# piezo_amplifier.net
KiCad netlist of a schematic drawn in EAGLE
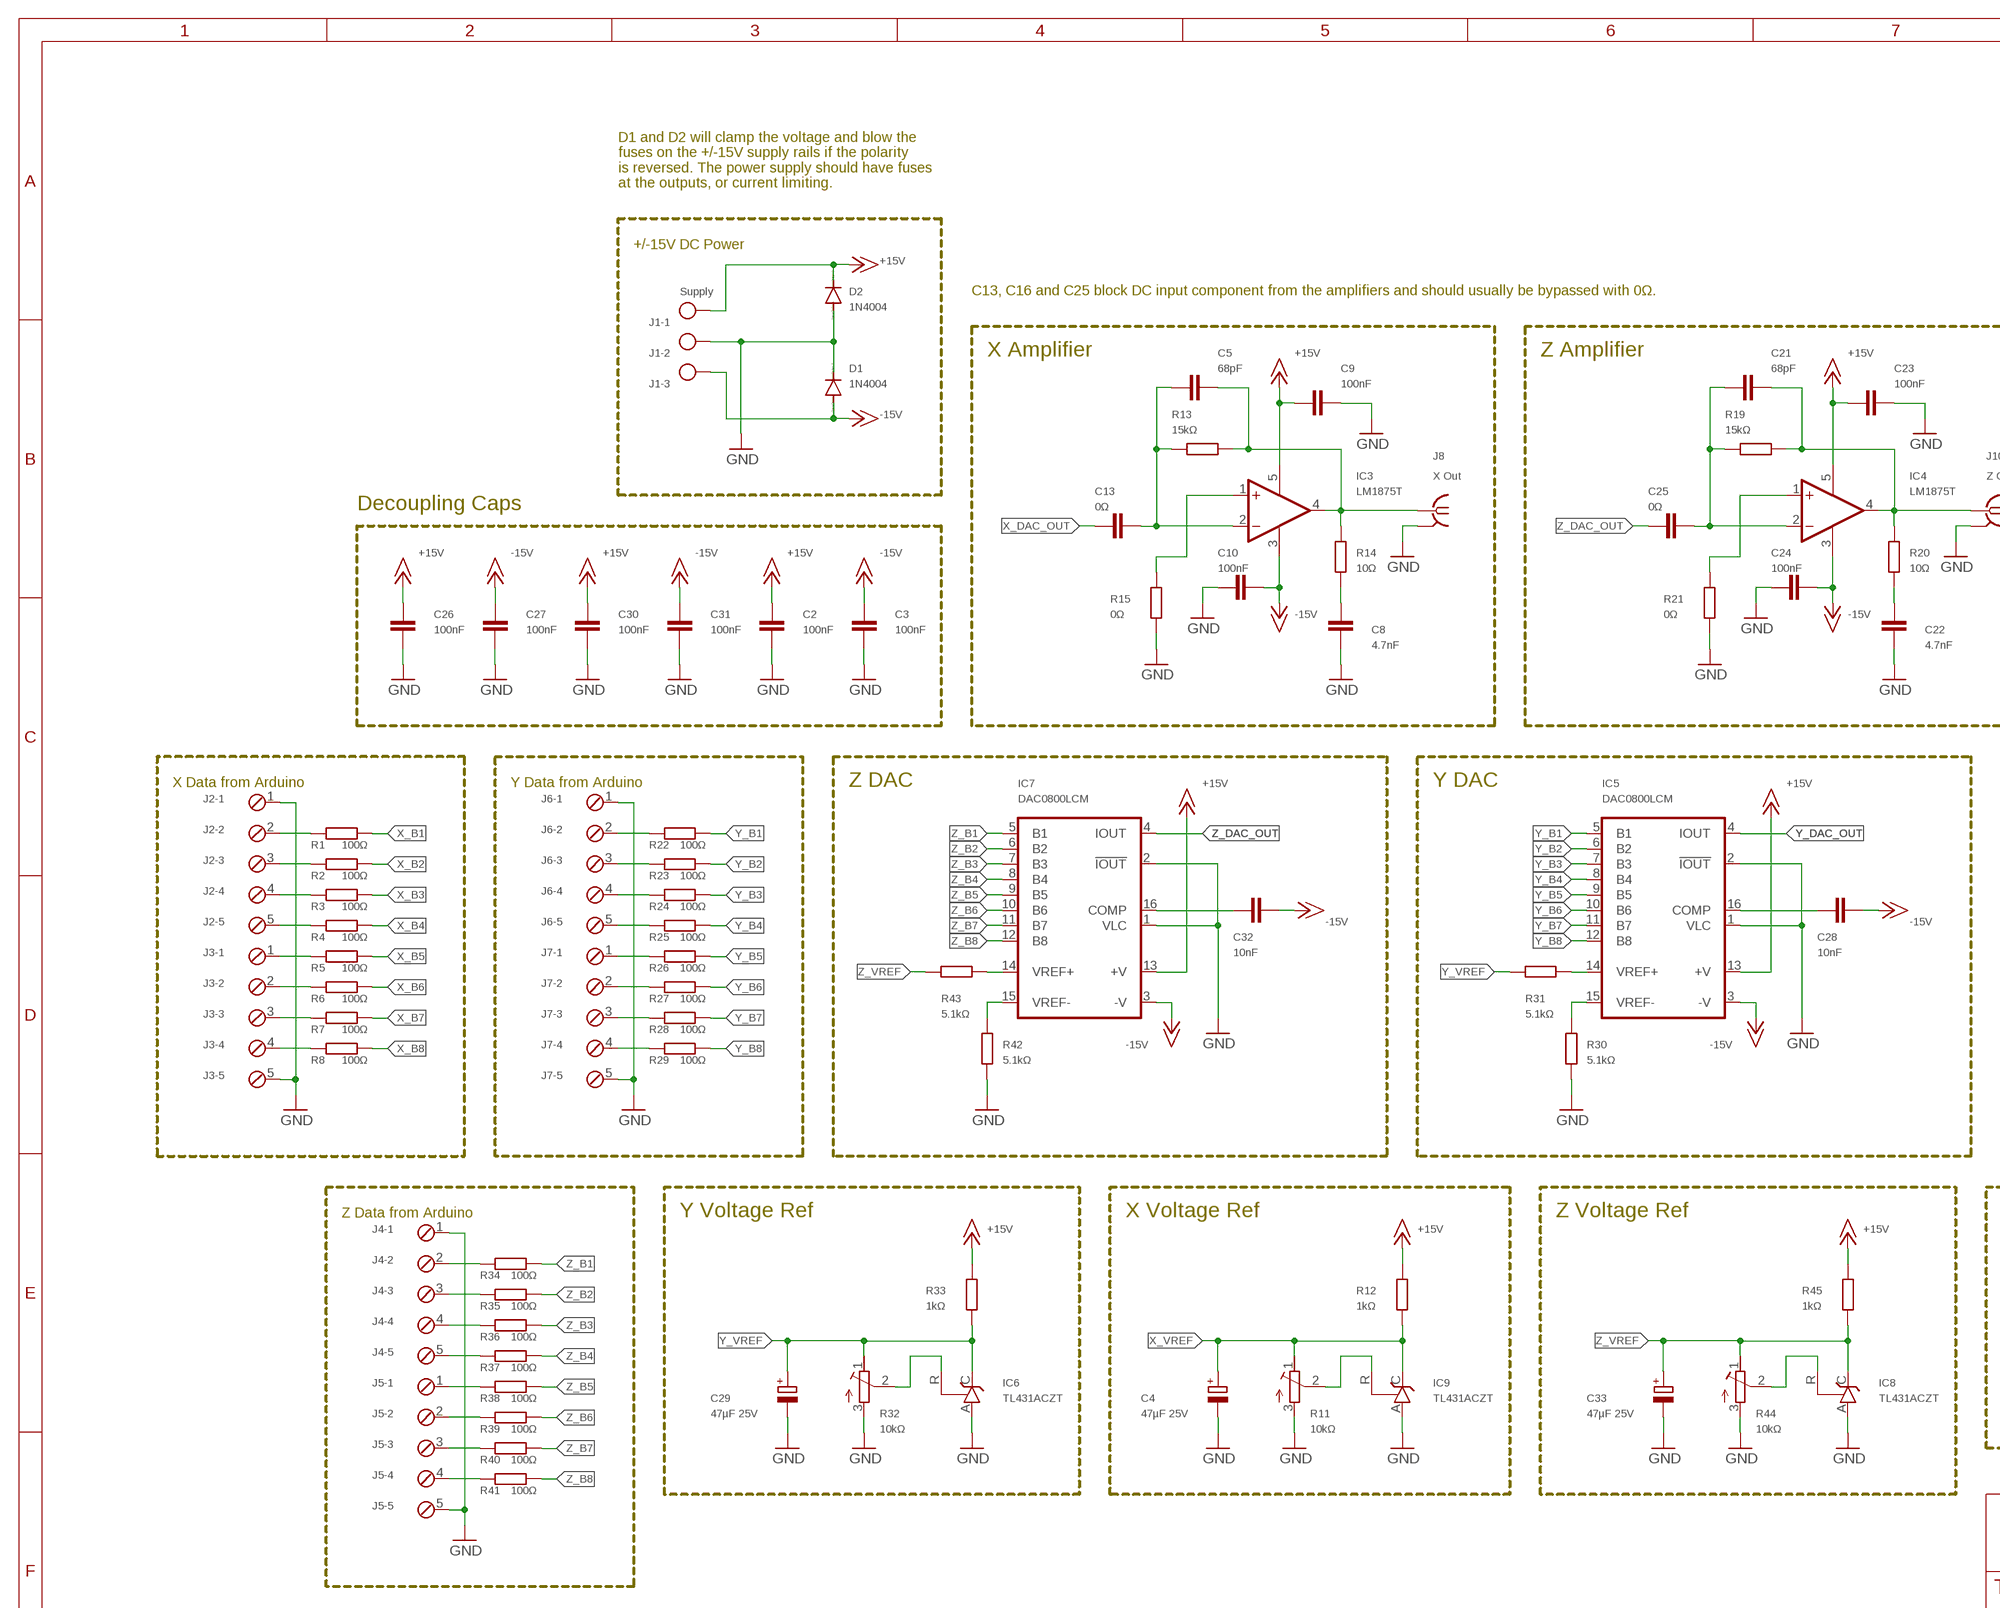
[diagram p0: schematic, sheet 1, part 1 of 3]
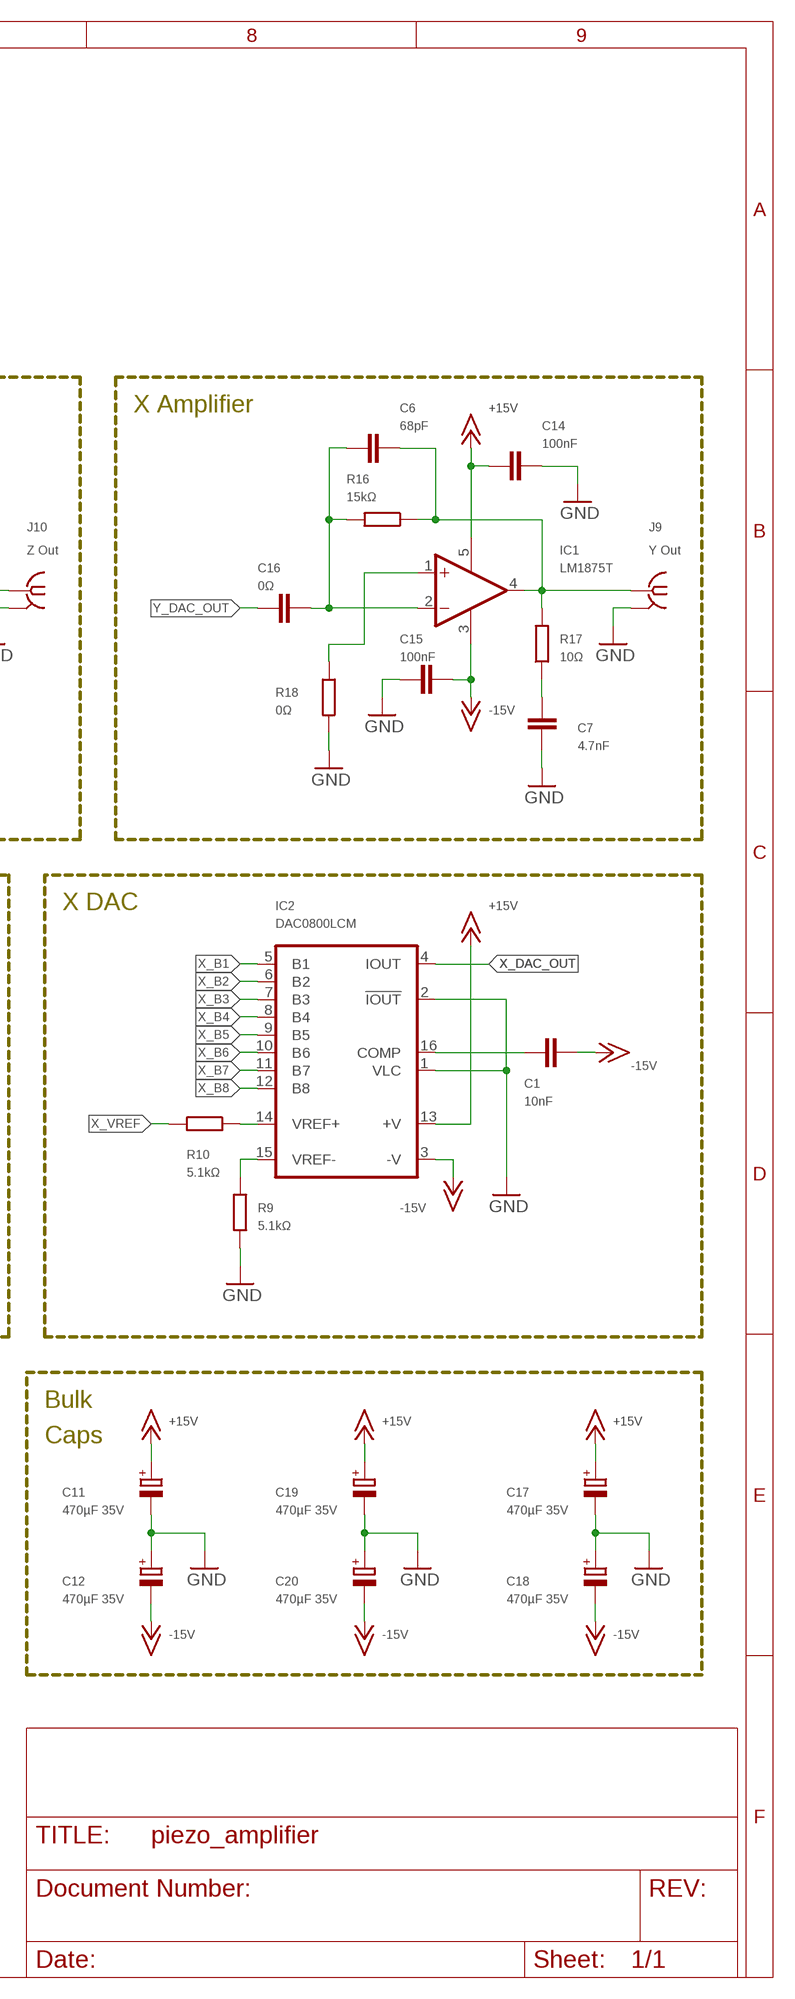
[diagram p1: schematic, sheet 1, part 2 of 3]
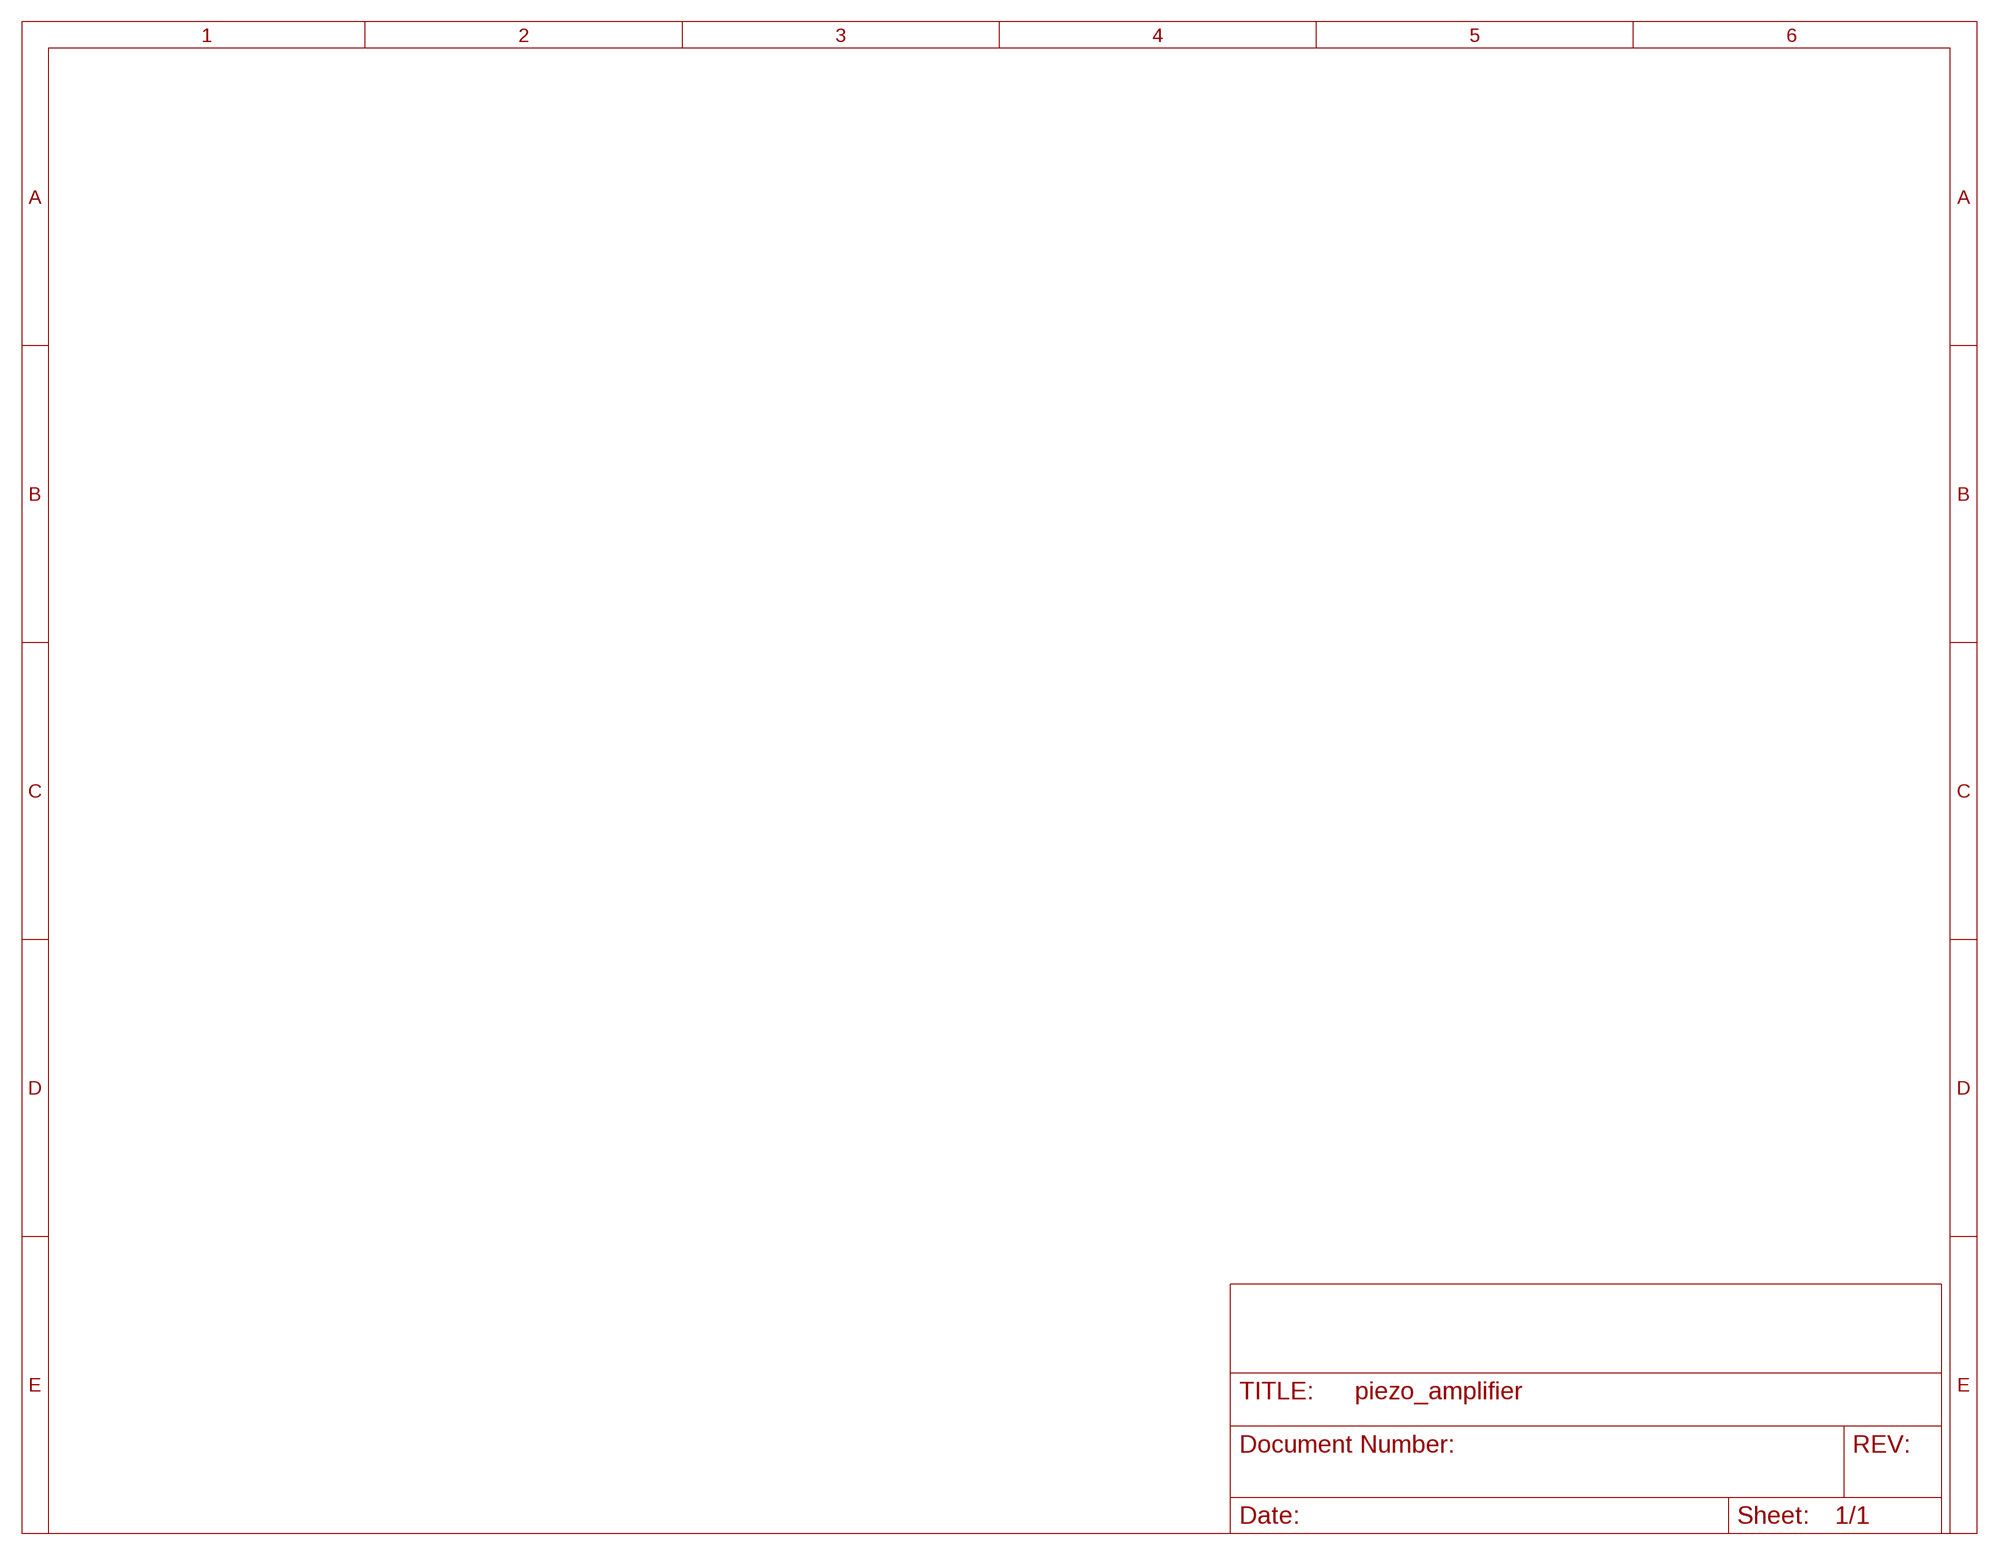
[diagram p2: schematic, sheet 1, part 3 of 3]

(export (version "E")
  (design (tool "Eeschema 10.0.6"))
  (components
    (comp (ref "C1")
      (value "10nF")
      (footprint "eagle-import:C050-025X075")
      (libsource (lib "eagle-import") (part "C-EU050-025X075"))
    )
    (comp (ref "C2")
      (value "100nF")
      (footprint "eagle-import:C050-025X075")
      (libsource (lib "eagle-import") (part "C-EU050-025X075"))
    )
    (comp (ref "C3")
      (value "100nF")
      (footprint "eagle-import:C050-025X075")
      (libsource (lib "eagle-import") (part "C-EU050-025X075"))
    )
    (comp (ref "C4")
      (value "47µF 25V")
      (footprint "eagle-import:E2,5-5")
      (libsource (lib "eagle-import") (part "CPOL-EUE2.5-5"))
    )
    (comp (ref "C5")
      (value "68pF")
      (footprint "eagle-import:C050-025X075")
      (libsource (lib "eagle-import") (part "C-EU050-025X075"))
    )
    (comp (ref "C6")
      (value "68pF")
      (footprint "eagle-import:C050-025X075")
      (libsource (lib "eagle-import") (part "C-EU050-025X075"))
    )
    (comp (ref "C7")
      (value "4.7nF")
      (footprint "eagle-import:C050-025X075")
      (libsource (lib "eagle-import") (part "C-EU050-025X075"))
    )
    (comp (ref "C8")
      (value "4.7nF")
      (footprint "eagle-import:C050-025X075")
      (libsource (lib "eagle-import") (part "C-EU050-025X075"))
    )
    (comp (ref "C9")
      (value "100nF")
      (footprint "eagle-import:C050-025X075")
      (libsource (lib "eagle-import") (part "C-EU050-025X075"))
    )
    (comp (ref "C10")
      (value "100nF")
      (footprint "eagle-import:C050-025X075")
      (libsource (lib "eagle-import") (part "C-EU050-025X075"))
    )
    (comp (ref "C11")
      (value "470µF 35V")
      (footprint "eagle-import:E5-8,5")
      (libsource (lib "eagle-import") (part "CPOL-EUE5-8.5"))
    )
    (comp (ref "C12")
      (value "470µF 35V")
      (footprint "eagle-import:E5-8,5")
      (libsource (lib "eagle-import") (part "CPOL-EUE5-8.5"))
    )
    (comp (ref "C13")
      (value "0Ω")
      (footprint "eagle-import:C050-025X075")
      (libsource (lib "eagle-import") (part "C-EU050-025X075"))
    )
    (comp (ref "C14")
      (value "100nF")
      (footprint "eagle-import:C050-025X075")
      (libsource (lib "eagle-import") (part "C-EU050-025X075"))
    )
    (comp (ref "C15")
      (value "100nF")
      (footprint "eagle-import:C050-025X075")
      (libsource (lib "eagle-import") (part "C-EU050-025X075"))
    )
    (comp (ref "C16")
      (value "0Ω")
      (footprint "eagle-import:C050-025X075")
      (libsource (lib "eagle-import") (part "C-EU050-025X075"))
    )
    (comp (ref "C17")
      (value "470µF 35V")
      (footprint "eagle-import:E5-8,5")
      (libsource (lib "eagle-import") (part "CPOL-EUE5-8.5"))
    )
    (comp (ref "C18")
      (value "470µF 35V")
      (footprint "eagle-import:E5-8,5")
      (libsource (lib "eagle-import") (part "CPOL-EUE5-8.5"))
    )
    (comp (ref "C19")
      (value "470µF 35V")
      (footprint "eagle-import:E5-8,5")
      (libsource (lib "eagle-import") (part "CPOL-EUE5-8.5"))
    )
    (comp (ref "C20")
      (value "470µF 35V")
      (footprint "eagle-import:E5-8,5")
      (libsource (lib "eagle-import") (part "CPOL-EUE5-8.5"))
    )
    (comp (ref "C21")
      (value "68pF")
      (footprint "eagle-import:C050-025X075")
      (libsource (lib "eagle-import") (part "C-EU050-025X075"))
    )
    (comp (ref "C22")
      (value "4.7nF")
      (footprint "eagle-import:C050-025X075")
      (libsource (lib "eagle-import") (part "C-EU050-025X075"))
    )
    (comp (ref "C23")
      (value "100nF")
      (footprint "eagle-import:C050-025X075")
      (libsource (lib "eagle-import") (part "C-EU050-025X075"))
    )
    (comp (ref "C24")
      (value "100nF")
      (footprint "eagle-import:C050-025X075")
      (libsource (lib "eagle-import") (part "C-EU050-025X075"))
    )
    (comp (ref "C25")
      (value "0Ω")
      (footprint "eagle-import:C050-025X075")
      (libsource (lib "eagle-import") (part "C-EU050-025X075"))
    )
    (comp (ref "C26")
      (value "100nF")
      (footprint "eagle-import:C050-025X075")
      (libsource (lib "eagle-import") (part "C-EU050-025X075"))
    )
    (comp (ref "C27")
      (value "100nF")
      (footprint "eagle-import:C050-025X075")
      (libsource (lib "eagle-import") (part "C-EU050-025X075"))
    )
    (comp (ref "C28")
      (value "10nF")
      (footprint "eagle-import:C050-025X075")
      (libsource (lib "eagle-import") (part "C-EU050-025X075"))
    )
    (comp (ref "C29")
      (value "47µF 25V")
      (footprint "eagle-import:E2,5-5")
      (libsource (lib "eagle-import") (part "CPOL-EUE2.5-5"))
    )
    (comp (ref "C30")
      (value "100nF")
      (footprint "eagle-import:C050-025X075")
      (libsource (lib "eagle-import") (part "C-EU050-025X075"))
    )
    (comp (ref "C31")
      (value "100nF")
      (footprint "eagle-import:C050-025X075")
      (libsource (lib "eagle-import") (part "C-EU050-025X075"))
    )
    (comp (ref "C32")
      (value "10nF")
      (footprint "eagle-import:C050-025X075")
      (libsource (lib "eagle-import") (part "C-EU050-025X075"))
    )
    (comp (ref "C33")
      (value "47µF 25V")
      (footprint "eagle-import:E2,5-5")
      (libsource (lib "eagle-import") (part "CPOL-EUE2.5-5"))
    )
    (comp (ref "D1")
      (value "1N4004")
      (footprint "eagle-import:DO41-10")
      (libsource (lib "eagle-import") (part "1N4004"))
    )
    (comp (ref "D2")
      (value "1N4004")
      (footprint "eagle-import:DO41-10")
      (libsource (lib "eagle-import") (part "1N4004"))
    )
    (comp (ref "IC1")
      (value "LM1875T")
      (footprint "eagle-import:CB367")
      (libsource (lib "eagle-import") (part "LM1875T"))
    )
    (comp (ref "IC2")
      (value "DAC0800LCM")
      (footprint "eagle-import:SO16")
      (libsource (lib "eagle-import") (part "DAC0800D"))
    )
    (comp (ref "IC3")
      (value "LM1875T")
      (footprint "eagle-import:CB367")
      (libsource (lib "eagle-import") (part "LM1875T"))
    )
    (comp (ref "IC4")
      (value "LM1875T")
      (footprint "eagle-import:CB367")
      (libsource (lib "eagle-import") (part "LM1875T"))
    )
    (comp (ref "IC5")
      (value "DAC0800LCM")
      (footprint "eagle-import:SO16")
      (libsource (lib "eagle-import") (part "DAC0800D"))
    )
    (comp (ref "IC6")
      (value "TL431ACZT")
      (footprint "eagle-import:TO92-CLP")
      (libsource (lib "eagle-import") (part "TL431CLP"))
    )
    (comp (ref "IC7")
      (value "DAC0800LCM")
      (footprint "eagle-import:SO16")
      (libsource (lib "eagle-import") (part "DAC0800D"))
    )
    (comp (ref "IC8")
      (value "TL431ACZT")
      (footprint "eagle-import:TO92-CLP")
      (libsource (lib "eagle-import") (part "TL431CLP"))
    )
    (comp (ref "IC9")
      (value "TL431ACZT")
      (footprint "eagle-import:TO92-CLP")
      (libsource (lib "eagle-import") (part "TL431CLP"))
    )
    (comp (ref "J1")
      (value "Supply")
      (footprint "eagle-import:MKDSN1,5_3-5,08")
      (libsource (lib "eagle-import") (part "MKDSN1,5/3-5,08"))
    )
    (comp (ref "J2")
      (value "MPT5")
      (footprint "eagle-import:5POL254")
      (libsource (lib "eagle-import") (part "MPT5"))
    )
    (comp (ref "J3")
      (value "MPT5")
      (footprint "eagle-import:5POL254")
      (libsource (lib "eagle-import") (part "MPT5"))
    )
    (comp (ref "J4")
      (value "MPT5")
      (footprint "eagle-import:5POL254")
      (libsource (lib "eagle-import") (part "MPT5"))
    )
    (comp (ref "J5")
      (value "MPT5")
      (footprint "eagle-import:5POL254")
      (libsource (lib "eagle-import") (part "MPT5"))
    )
    (comp (ref "J6")
      (value "MPT5")
      (footprint "eagle-import:5POL254")
      (libsource (lib "eagle-import") (part "MPT5"))
    )
    (comp (ref "J7")
      (value "MPT5")
      (footprint "eagle-import:5POL254")
      (libsource (lib "eagle-import") (part "MPT5"))
    )
    (comp (ref "J8")
      (value "X Out")
      (footprint "eagle-import:BU-SMA-V")
      (libsource (lib "eagle-import") (part "BU-SMA-V"))
    )
    (comp (ref "J9")
      (value "Y Out")
      (footprint "eagle-import:BU-SMA-V")
      (libsource (lib "eagle-import") (part "BU-SMA-V"))
    )
    (comp (ref "J10")
      (value "Z Out")
      (footprint "eagle-import:BU-SMA-V")
      (libsource (lib "eagle-import") (part "BU-SMA-V"))
    )
    (comp (ref "R1")
      (value "100Ω")
      (footprint "eagle-import:0207_10")
      (libsource (lib "eagle-import") (part "R-EU_0207/10"))
    )
    (comp (ref "R2")
      (value "100Ω")
      (footprint "eagle-import:0207_10")
      (libsource (lib "eagle-import") (part "R-EU_0207/10"))
    )
    (comp (ref "R3")
      (value "100Ω")
      (footprint "eagle-import:0207_10")
      (libsource (lib "eagle-import") (part "R-EU_0207/10"))
    )
    (comp (ref "R4")
      (value "100Ω")
      (footprint "eagle-import:0207_10")
      (libsource (lib "eagle-import") (part "R-EU_0207/10"))
    )
    (comp (ref "R5")
      (value "100Ω")
      (footprint "eagle-import:0207_10")
      (libsource (lib "eagle-import") (part "R-EU_0207/10"))
    )
    (comp (ref "R6")
      (value "100Ω")
      (footprint "eagle-import:0207_10")
      (libsource (lib "eagle-import") (part "R-EU_0207/10"))
    )
    (comp (ref "R7")
      (value "100Ω")
      (footprint "eagle-import:0207_10")
      (libsource (lib "eagle-import") (part "R-EU_0207/10"))
    )
    (comp (ref "R8")
      (value "100Ω")
      (footprint "eagle-import:0207_10")
      (libsource (lib "eagle-import") (part "R-EU_0207/10"))
    )
    (comp (ref "R9")
      (value "5.1kΩ")
      (footprint "eagle-import:0207_10")
      (libsource (lib "eagle-import") (part "R-EU_0207/10"))
    )
    (comp (ref "R10")
      (value "5.1kΩ")
      (footprint "eagle-import:0207_10")
      (libsource (lib "eagle-import") (part "R-EU_0207/10"))
    )
    (comp (ref "R11")
      (value "10kΩ")
      (footprint "eagle-import:RTRIMT93YA")
      (libsource (lib "eagle-import") (part "R-TRIMMT93YA"))
    )
    (comp (ref "R12")
      (value "1kΩ")
      (footprint "eagle-import:0207_10")
      (libsource (lib "eagle-import") (part "R-EU_0207/10"))
    )
    (comp (ref "R13")
      (value "15kΩ")
      (footprint "eagle-import:0207_10")
      (libsource (lib "eagle-import") (part "R-EU_0207/10"))
    )
    (comp (ref "R14")
      (value "10Ω")
      (footprint "eagle-import:0207_10")
      (libsource (lib "eagle-import") (part "R-EU_0207/10"))
    )
    (comp (ref "R15")
      (value "0Ω")
      (footprint "eagle-import:0207_10")
      (libsource (lib "eagle-import") (part "R-EU_0207/10"))
    )
    (comp (ref "R16")
      (value "15kΩ")
      (footprint "eagle-import:0207_10")
      (libsource (lib "eagle-import") (part "R-EU_0207/10"))
    )
    (comp (ref "R17")
      (value "10Ω")
      (footprint "eagle-import:0207_10")
      (libsource (lib "eagle-import") (part "R-EU_0207/10"))
    )
    (comp (ref "R18")
      (value "0Ω")
      (footprint "eagle-import:0207_10")
      (libsource (lib "eagle-import") (part "R-EU_0207/10"))
    )
    (comp (ref "R19")
      (value "15kΩ")
      (footprint "eagle-import:0207_10")
      (libsource (lib "eagle-import") (part "R-EU_0207/10"))
    )
    (comp (ref "R20")
      (value "10Ω")
      (footprint "eagle-import:0207_10")
      (libsource (lib "eagle-import") (part "R-EU_0207/10"))
    )
    (comp (ref "R21")
      (value "0Ω")
      (footprint "eagle-import:0207_10")
      (libsource (lib "eagle-import") (part "R-EU_0207/10"))
    )
    (comp (ref "R22")
      (value "100Ω")
      (footprint "eagle-import:0207_10")
      (libsource (lib "eagle-import") (part "R-EU_0207/10"))
    )
    (comp (ref "R23")
      (value "100Ω")
      (footprint "eagle-import:0207_10")
      (libsource (lib "eagle-import") (part "R-EU_0207/10"))
    )
    (comp (ref "R24")
      (value "100Ω")
      (footprint "eagle-import:0207_10")
      (libsource (lib "eagle-import") (part "R-EU_0207/10"))
    )
    (comp (ref "R25")
      (value "100Ω")
      (footprint "eagle-import:0207_10")
      (libsource (lib "eagle-import") (part "R-EU_0207/10"))
    )
    (comp (ref "R26")
      (value "100Ω")
      (footprint "eagle-import:0207_10")
      (libsource (lib "eagle-import") (part "R-EU_0207/10"))
    )
    (comp (ref "R27")
      (value "100Ω")
      (footprint "eagle-import:0207_10")
      (libsource (lib "eagle-import") (part "R-EU_0207/10"))
    )
    (comp (ref "R28")
      (value "100Ω")
      (footprint "eagle-import:0207_10")
      (libsource (lib "eagle-import") (part "R-EU_0207/10"))
    )
    (comp (ref "R29")
      (value "100Ω")
      (footprint "eagle-import:0207_10")
      (libsource (lib "eagle-import") (part "R-EU_0207/10"))
    )
    (comp (ref "R30")
      (value "5.1kΩ")
      (footprint "eagle-import:0207_10")
      (libsource (lib "eagle-import") (part "R-EU_0207/10"))
    )
    (comp (ref "R31")
      (value "5.1kΩ")
      (footprint "eagle-import:0207_10")
      (libsource (lib "eagle-import") (part "R-EU_0207/10"))
    )
    (comp (ref "R32")
      (value "10kΩ")
      (footprint "eagle-import:RTRIMT93YA")
      (libsource (lib "eagle-import") (part "R-TRIMMT93YA"))
    )
    (comp (ref "R33")
      (value "1kΩ")
      (footprint "eagle-import:0207_10")
      (libsource (lib "eagle-import") (part "R-EU_0207/10"))
    )
    (comp (ref "R34")
      (value "100Ω")
      (footprint "eagle-import:0207_10")
      (libsource (lib "eagle-import") (part "R-EU_0207/10"))
    )
    (comp (ref "R35")
      (value "100Ω")
      (footprint "eagle-import:0207_10")
      (libsource (lib "eagle-import") (part "R-EU_0207/10"))
    )
    (comp (ref "R36")
      (value "100Ω")
      (footprint "eagle-import:0207_10")
      (libsource (lib "eagle-import") (part "R-EU_0207/10"))
    )
    (comp (ref "R37")
      (value "100Ω")
      (footprint "eagle-import:0207_10")
      (libsource (lib "eagle-import") (part "R-EU_0207/10"))
    )
    (comp (ref "R38")
      (value "100Ω")
      (footprint "eagle-import:0207_10")
      (libsource (lib "eagle-import") (part "R-EU_0207/10"))
    )
    (comp (ref "R39")
      (value "100Ω")
      (footprint "eagle-import:0207_10")
      (libsource (lib "eagle-import") (part "R-EU_0207/10"))
    )
    (comp (ref "R40")
      (value "100Ω")
      (footprint "eagle-import:0207_10")
      (libsource (lib "eagle-import") (part "R-EU_0207/10"))
    )
    (comp (ref "R41")
      (value "100Ω")
      (footprint "eagle-import:0207_10")
      (libsource (lib "eagle-import") (part "R-EU_0207/10"))
    )
    (comp (ref "R42")
      (value "5.1kΩ")
      (footprint "eagle-import:0207_10")
      (libsource (lib "eagle-import") (part "R-EU_0207/10"))
    )
    (comp (ref "R43")
      (value "5.1kΩ")
      (footprint "eagle-import:0207_10")
      (libsource (lib "eagle-import") (part "R-EU_0207/10"))
    )
    (comp (ref "R44")
      (value "10kΩ")
      (footprint "eagle-import:RTRIMT93YA")
      (libsource (lib "eagle-import") (part "R-TRIMMT93YA"))
    )
    (comp (ref "R45")
      (value "1kΩ")
      (footprint "eagle-import:0207_10")
      (libsource (lib "eagle-import") (part "R-EU_0207/10"))
    )
  )
  (nets
    (net (code "1") (name "+15V") (class "Default")
      (node (ref "C11") (pin "+") (pinfunction "+_+") (pintype "passive"))
      (node (ref "C14") (pin "1") (pinfunction "1_1") (pintype "passive"))
      (node (ref "C17") (pin "+") (pinfunction "+_+") (pintype "passive"))
      (node (ref "C19") (pin "+") (pinfunction "+_+") (pintype "passive"))
      (node (ref "C2") (pin "2") (pinfunction "2_2") (pintype "passive"))
      (node (ref "C23") (pin "1") (pinfunction "1_1") (pintype "passive"))
      (node (ref "C26") (pin "2") (pinfunction "2_2") (pintype "passive"))
      (node (ref "C30") (pin "2") (pinfunction "2_2") (pintype "passive"))
      (node (ref "C9") (pin "1") (pinfunction "1_1") (pintype "passive"))
      (node (ref "D2") (pin "C") (pinfunction "C_C") (pintype "passive"))
      (node (ref "IC1") (pin "5") (pinfunction "V+_5") (pintype "power_in"))
      (node (ref "IC2") (pin "13") (pinfunction "+V_13") (pintype "power_in"))
      (node (ref "IC3") (pin "5") (pinfunction "V+_5") (pintype "power_in"))
      (node (ref "IC4") (pin "5") (pinfunction "V+_5") (pintype "power_in"))
      (node (ref "IC5") (pin "13") (pinfunction "+V_13") (pintype "power_in"))
      (node (ref "IC7") (pin "13") (pinfunction "+V_13") (pintype "power_in"))
      (node (ref "J1") (pin "1") (pinfunction "KL_1") (pintype "passive"))
      (node (ref "R12") (pin "2") (pinfunction "2_2") (pintype "passive"))
      (node (ref "R33") (pin "2") (pinfunction "2_2") (pintype "passive"))
      (node (ref "R45") (pin "2") (pinfunction "2_2") (pintype "passive"))
    )
    (net (code "2") (name "-15V") (class "Default")
      (node (ref "C1") (pin "2") (pinfunction "2_2") (pintype "passive"))
      (node (ref "C10") (pin "2") (pinfunction "2_2") (pintype "passive"))
      (node (ref "C12") (pin "-") (pinfunction "-_-") (pintype "passive"))
      (node (ref "C15") (pin "2") (pinfunction "2_2") (pintype "passive"))
      (node (ref "C18") (pin "-") (pinfunction "-_-") (pintype "passive"))
      (node (ref "C20") (pin "-") (pinfunction "-_-") (pintype "passive"))
      (node (ref "C24") (pin "2") (pinfunction "2_2") (pintype "passive"))
      (node (ref "C27") (pin "2") (pinfunction "2_2") (pintype "passive"))
      (node (ref "C28") (pin "2") (pinfunction "2_2") (pintype "passive"))
      (node (ref "C3") (pin "2") (pinfunction "2_2") (pintype "passive"))
      (node (ref "C31") (pin "2") (pinfunction "2_2") (pintype "passive"))
      (node (ref "C32") (pin "2") (pinfunction "2_2") (pintype "passive"))
      (node (ref "D1") (pin "A") (pinfunction "A_A") (pintype "passive"))
      (node (ref "IC1") (pin "3") (pinfunction "V-_3") (pintype "power_in"))
      (node (ref "IC2") (pin "3") (pinfunction "-V_3") (pintype "power_in"))
      (node (ref "IC3") (pin "3") (pinfunction "V-_3") (pintype "power_in"))
      (node (ref "IC4") (pin "3") (pinfunction "V-_3") (pintype "power_in"))
      (node (ref "IC5") (pin "3") (pinfunction "-V_3") (pintype "power_in"))
      (node (ref "IC7") (pin "3") (pinfunction "-V_3") (pintype "power_in"))
      (node (ref "J1") (pin "3") (pinfunction "KL_3") (pintype "passive"))
    )
    (net (code "3") (name "GND") (class "Default")
      (node (ref "C10") (pin "1") (pinfunction "1_1") (pintype "passive"))
      (node (ref "C11") (pin "-") (pinfunction "-_-") (pintype "passive"))
      (node (ref "C12") (pin "+") (pinfunction "+_+") (pintype "passive"))
      (node (ref "C14") (pin "2") (pinfunction "2_2") (pintype "passive"))
      (node (ref "C15") (pin "1") (pinfunction "1_1") (pintype "passive"))
      (node (ref "C17") (pin "-") (pinfunction "-_-") (pintype "passive"))
      (node (ref "C18") (pin "+") (pinfunction "+_+") (pintype "passive"))
      (node (ref "C19") (pin "-") (pinfunction "-_-") (pintype "passive"))
      (node (ref "C2") (pin "1") (pinfunction "1_1") (pintype "passive"))
      (node (ref "C20") (pin "+") (pinfunction "+_+") (pintype "passive"))
      (node (ref "C22") (pin "2") (pinfunction "2_2") (pintype "passive"))
      (node (ref "C23") (pin "2") (pinfunction "2_2") (pintype "passive"))
      (node (ref "C24") (pin "1") (pinfunction "1_1") (pintype "passive"))
      (node (ref "C26") (pin "1") (pinfunction "1_1") (pintype "passive"))
      (node (ref "C27") (pin "1") (pinfunction "1_1") (pintype "passive"))
      (node (ref "C29") (pin "-") (pinfunction "-_-") (pintype "passive"))
      (node (ref "C3") (pin "1") (pinfunction "1_1") (pintype "passive"))
      (node (ref "C30") (pin "1") (pinfunction "1_1") (pintype "passive"))
      (node (ref "C31") (pin "1") (pinfunction "1_1") (pintype "passive"))
      (node (ref "C33") (pin "-") (pinfunction "-_-") (pintype "passive"))
      (node (ref "C4") (pin "-") (pinfunction "-_-") (pintype "passive"))
      (node (ref "C7") (pin "2") (pinfunction "2_2") (pintype "passive"))
      (node (ref "C8") (pin "2") (pinfunction "2_2") (pintype "passive"))
      (node (ref "C9") (pin "2") (pinfunction "2_2") (pintype "passive"))
      (node (ref "D1") (pin "C") (pinfunction "C_C") (pintype "passive"))
      (node (ref "D2") (pin "A") (pinfunction "A_A") (pintype "passive"))
      (node (ref "IC2") (pin "1") (pinfunction "VLC_1") (pintype "input"))
      (node (ref "IC2") (pin "2") (pinfunction "~{IOUT}_2") (pintype "output"))
      (node (ref "IC5") (pin "1") (pinfunction "VLC_1") (pintype "input"))
      (node (ref "IC5") (pin "2") (pinfunction "~{IOUT}_2") (pintype "output"))
      (node (ref "IC6") (pin "A") (pinfunction "A_A") (pintype "passive"))
      (node (ref "IC7") (pin "1") (pinfunction "VLC_1") (pintype "input"))
      (node (ref "IC7") (pin "2") (pinfunction "~{IOUT}_2") (pintype "output"))
      (node (ref "IC8") (pin "A") (pinfunction "A_A") (pintype "passive"))
      (node (ref "IC9") (pin "A") (pinfunction "A_A") (pintype "passive"))
      (node (ref "J1") (pin "2") (pinfunction "KL_2") (pintype "passive"))
      (node (ref "J10") (pin "2") (pinfunction "2_2") (pintype "passive"))
      (node (ref "J10") (pin "3") (pinfunction "2_3") (pintype "passive"))
      (node (ref "J10") (pin "4") (pinfunction "2_4") (pintype "passive"))
      (node (ref "J10") (pin "5") (pinfunction "2_5") (pintype "passive"))
      (node (ref "J2") (pin "1") (pinfunction "1_1") (pintype "passive"))
      (node (ref "J3") (pin "5") (pinfunction "1_5") (pintype "passive"))
      (node (ref "J4") (pin "1") (pinfunction "1_1") (pintype "passive"))
      (node (ref "J5") (pin "5") (pinfunction "1_5") (pintype "passive"))
      (node (ref "J6") (pin "1") (pinfunction "1_1") (pintype "passive"))
      (node (ref "J7") (pin "5") (pinfunction "1_5") (pintype "passive"))
      (node (ref "J8") (pin "2") (pinfunction "2_2") (pintype "passive"))
      (node (ref "J8") (pin "3") (pinfunction "2_3") (pintype "passive"))
      (node (ref "J8") (pin "4") (pinfunction "2_4") (pintype "passive"))
      (node (ref "J8") (pin "5") (pinfunction "2_5") (pintype "passive"))
      (node (ref "J9") (pin "2") (pinfunction "2_2") (pintype "passive"))
      (node (ref "J9") (pin "3") (pinfunction "2_3") (pintype "passive"))
      (node (ref "J9") (pin "4") (pinfunction "2_4") (pintype "passive"))
      (node (ref "J9") (pin "5") (pinfunction "2_5") (pintype "passive"))
      (node (ref "R11") (pin "3") (pinfunction "A_3") (pintype "passive"))
      (node (ref "R15") (pin "2") (pinfunction "2_2") (pintype "passive"))
      (node (ref "R18") (pin "2") (pinfunction "2_2") (pintype "passive"))
      (node (ref "R21") (pin "2") (pinfunction "2_2") (pintype "passive"))
      (node (ref "R30") (pin "1") (pinfunction "1_1") (pintype "passive"))
      (node (ref "R32") (pin "3") (pinfunction "A_3") (pintype "passive"))
      (node (ref "R42") (pin "1") (pinfunction "1_1") (pintype "passive"))
      (node (ref "R44") (pin "3") (pinfunction "A_3") (pintype "passive"))
      (node (ref "R9") (pin "1") (pinfunction "1_1") (pintype "passive"))
    )
    (net (code "4") (name "Net-(C7-Pad1)") (class "Default")
      (node (ref "C7") (pin "1") (pinfunction "1_1") (pintype "passive"))
      (node (ref "R17") (pin "1") (pinfunction "1_1") (pintype "passive"))
    )
    (net (code "5") (name "Net-(C8-Pad1)") (class "Default")
      (node (ref "C8") (pin "1") (pinfunction "1_1") (pintype "passive"))
      (node (ref "R14") (pin "1") (pinfunction "1_1") (pintype "passive"))
    )
    (net (code "6") (name "Net-(C22-Pad1)") (class "Default")
      (node (ref "C22") (pin "1") (pinfunction "1_1") (pintype "passive"))
      (node (ref "R20") (pin "1") (pinfunction "1_1") (pintype "passive"))
    )
    (net (code "7") (name "Net-(IC1-+IN)") (class "Default")
      (node (ref "IC1") (pin "1") (pinfunction "+IN_1") (pintype "input"))
      (node (ref "R18") (pin "1") (pinfunction "1_1") (pintype "passive"))
    )
    (net (code "8") (name "Net-(IC1--IN)") (class "Default")
      (node (ref "C16") (pin "1") (pinfunction "1_1") (pintype "passive"))
      (node (ref "C6") (pin "2") (pinfunction "2_2") (pintype "passive"))
      (node (ref "IC1") (pin "2") (pinfunction "-IN_2") (pintype "input"))
      (node (ref "R16") (pin "2") (pinfunction "2_2") (pintype "passive"))
    )
    (net (code "9") (name "Net-(IC1-OUT)") (class "Default")
      (node (ref "C6") (pin "1") (pinfunction "1_1") (pintype "passive"))
      (node (ref "IC1") (pin "4") (pinfunction "OUT_4") (pintype "output"))
      (node (ref "J9") (pin "1") (pinfunction "1_1") (pintype "passive"))
      (node (ref "R16") (pin "1") (pinfunction "1_1") (pintype "passive"))
      (node (ref "R17") (pin "2") (pinfunction "2_2") (pintype "passive"))
    )
    (net (code "10") (name "Net-(IC2-COMP)") (class "Default")
      (node (ref "C1") (pin "1") (pinfunction "1_1") (pintype "passive"))
      (node (ref "IC2") (pin "16") (pinfunction "COMP_16") (pintype "input"))
    )
    (net (code "11") (name "Net-(IC2-VREF+)") (class "Default")
      (node (ref "IC2") (pin "14") (pinfunction "VREF+_14") (pintype "input"))
      (node (ref "R10") (pin "1") (pinfunction "1_1") (pintype "passive"))
    )
    (net (code "12") (name "Net-(IC2-VREF-)") (class "Default")
      (node (ref "IC2") (pin "15") (pinfunction "VREF-_15") (pintype "input"))
      (node (ref "R9") (pin "2") (pinfunction "2_2") (pintype "passive"))
    )
    (net (code "13") (name "Net-(IC3-+IN)") (class "Default")
      (node (ref "IC3") (pin "1") (pinfunction "+IN_1") (pintype "input"))
      (node (ref "R15") (pin "1") (pinfunction "1_1") (pintype "passive"))
    )
    (net (code "14") (name "Net-(IC3--IN)") (class "Default")
      (node (ref "C13") (pin "1") (pinfunction "1_1") (pintype "passive"))
      (node (ref "C5") (pin "2") (pinfunction "2_2") (pintype "passive"))
      (node (ref "IC3") (pin "2") (pinfunction "-IN_2") (pintype "input"))
      (node (ref "R13") (pin "2") (pinfunction "2_2") (pintype "passive"))
    )
    (net (code "15") (name "Net-(IC3-OUT)") (class "Default")
      (node (ref "C5") (pin "1") (pinfunction "1_1") (pintype "passive"))
      (node (ref "IC3") (pin "4") (pinfunction "OUT_4") (pintype "output"))
      (node (ref "J8") (pin "1") (pinfunction "1_1") (pintype "passive"))
      (node (ref "R13") (pin "1") (pinfunction "1_1") (pintype "passive"))
      (node (ref "R14") (pin "2") (pinfunction "2_2") (pintype "passive"))
    )
    (net (code "16") (name "Net-(IC4-+IN)") (class "Default")
      (node (ref "IC4") (pin "1") (pinfunction "+IN_1") (pintype "input"))
      (node (ref "R21") (pin "1") (pinfunction "1_1") (pintype "passive"))
    )
    (net (code "17") (name "Net-(IC4--IN)") (class "Default")
      (node (ref "C21") (pin "2") (pinfunction "2_2") (pintype "passive"))
      (node (ref "C25") (pin "1") (pinfunction "1_1") (pintype "passive"))
      (node (ref "IC4") (pin "2") (pinfunction "-IN_2") (pintype "input"))
      (node (ref "R19") (pin "2") (pinfunction "2_2") (pintype "passive"))
    )
    (net (code "18") (name "Net-(IC4-OUT)") (class "Default")
      (node (ref "C21") (pin "1") (pinfunction "1_1") (pintype "passive"))
      (node (ref "IC4") (pin "4") (pinfunction "OUT_4") (pintype "output"))
      (node (ref "J10") (pin "1") (pinfunction "1_1") (pintype "passive"))
      (node (ref "R19") (pin "1") (pinfunction "1_1") (pintype "passive"))
      (node (ref "R20") (pin "2") (pinfunction "2_2") (pintype "passive"))
    )
    (net (code "19") (name "Net-(IC5-COMP)") (class "Default")
      (node (ref "C28") (pin "1") (pinfunction "1_1") (pintype "passive"))
      (node (ref "IC5") (pin "16") (pinfunction "COMP_16") (pintype "input"))
    )
    (net (code "20") (name "Net-(IC5-VREF+)") (class "Default")
      (node (ref "IC5") (pin "14") (pinfunction "VREF+_14") (pintype "input"))
      (node (ref "R31") (pin "1") (pinfunction "1_1") (pintype "passive"))
    )
    (net (code "21") (name "Net-(IC5-VREF-)") (class "Default")
      (node (ref "IC5") (pin "15") (pinfunction "VREF-_15") (pintype "input"))
      (node (ref "R30") (pin "2") (pinfunction "2_2") (pintype "passive"))
    )
    (net (code "22") (name "Net-(IC7-COMP)") (class "Default")
      (node (ref "C32") (pin "1") (pinfunction "1_1") (pintype "passive"))
      (node (ref "IC7") (pin "16") (pinfunction "COMP_16") (pintype "input"))
    )
    (net (code "23") (name "Net-(IC7-VREF+)") (class "Default")
      (node (ref "IC7") (pin "14") (pinfunction "VREF+_14") (pintype "input"))
      (node (ref "R43") (pin "1") (pinfunction "1_1") (pintype "passive"))
    )
    (net (code "24") (name "Net-(IC7-VREF-)") (class "Default")
      (node (ref "IC7") (pin "15") (pinfunction "VREF-_15") (pintype "input"))
      (node (ref "R42") (pin "2") (pinfunction "2_2") (pintype "passive"))
    )
    (net (code "25") (name "Net-(J2B-1)") (class "Default")
      (node (ref "J2") (pin "2") (pinfunction "1_2") (pintype "passive"))
      (node (ref "R1") (pin "1") (pinfunction "1_1") (pintype "passive"))
    )
    (net (code "26") (name "Net-(J2C-1)") (class "Default")
      (node (ref "J2") (pin "3") (pinfunction "1_3") (pintype "passive"))
      (node (ref "R2") (pin "1") (pinfunction "1_1") (pintype "passive"))
    )
    (net (code "27") (name "Net-(J2D-1)") (class "Default")
      (node (ref "J2") (pin "4") (pinfunction "1_4") (pintype "passive"))
      (node (ref "R3") (pin "1") (pinfunction "1_1") (pintype "passive"))
    )
    (net (code "28") (name "Net-(J2E-1)") (class "Default")
      (node (ref "J2") (pin "5") (pinfunction "1_5") (pintype "passive"))
      (node (ref "R4") (pin "1") (pinfunction "1_1") (pintype "passive"))
    )
    (net (code "29") (name "Net-(J3-Pad1)") (class "Default")
      (node (ref "J3") (pin "1") (pinfunction "1_1") (pintype "passive"))
      (node (ref "R5") (pin "1") (pinfunction "1_1") (pintype "passive"))
    )
    (net (code "30") (name "Net-(J3B-1)") (class "Default")
      (node (ref "J3") (pin "2") (pinfunction "1_2") (pintype "passive"))
      (node (ref "R6") (pin "1") (pinfunction "1_1") (pintype "passive"))
    )
    (net (code "31") (name "Net-(J3C-1)") (class "Default")
      (node (ref "J3") (pin "3") (pinfunction "1_3") (pintype "passive"))
      (node (ref "R7") (pin "1") (pinfunction "1_1") (pintype "passive"))
    )
    (net (code "32") (name "Net-(J3D-1)") (class "Default")
      (node (ref "J3") (pin "4") (pinfunction "1_4") (pintype "passive"))
      (node (ref "R8") (pin "1") (pinfunction "1_1") (pintype "passive"))
    )
    (net (code "33") (name "Net-(J4B-1)") (class "Default")
      (node (ref "J4") (pin "2") (pinfunction "1_2") (pintype "passive"))
      (node (ref "R34") (pin "1") (pinfunction "1_1") (pintype "passive"))
    )
    (net (code "34") (name "Net-(J4C-1)") (class "Default")
      (node (ref "J4") (pin "3") (pinfunction "1_3") (pintype "passive"))
      (node (ref "R35") (pin "1") (pinfunction "1_1") (pintype "passive"))
    )
    (net (code "35") (name "Net-(J4D-1)") (class "Default")
      (node (ref "J4") (pin "4") (pinfunction "1_4") (pintype "passive"))
      (node (ref "R36") (pin "1") (pinfunction "1_1") (pintype "passive"))
    )
    (net (code "36") (name "Net-(J4E-1)") (class "Default")
      (node (ref "J4") (pin "5") (pinfunction "1_5") (pintype "passive"))
      (node (ref "R37") (pin "1") (pinfunction "1_1") (pintype "passive"))
    )
    (net (code "37") (name "Net-(J5-Pad1)") (class "Default")
      (node (ref "J5") (pin "1") (pinfunction "1_1") (pintype "passive"))
      (node (ref "R38") (pin "1") (pinfunction "1_1") (pintype "passive"))
    )
    (net (code "38") (name "Net-(J5B-1)") (class "Default")
      (node (ref "J5") (pin "2") (pinfunction "1_2") (pintype "passive"))
      (node (ref "R39") (pin "1") (pinfunction "1_1") (pintype "passive"))
    )
    (net (code "39") (name "Net-(J5C-1)") (class "Default")
      (node (ref "J5") (pin "3") (pinfunction "1_3") (pintype "passive"))
      (node (ref "R40") (pin "1") (pinfunction "1_1") (pintype "passive"))
    )
    (net (code "40") (name "Net-(J5D-1)") (class "Default")
      (node (ref "J5") (pin "4") (pinfunction "1_4") (pintype "passive"))
      (node (ref "R41") (pin "1") (pinfunction "1_1") (pintype "passive"))
    )
    (net (code "41") (name "Net-(J6B-1)") (class "Default")
      (node (ref "J6") (pin "2") (pinfunction "1_2") (pintype "passive"))
      (node (ref "R22") (pin "1") (pinfunction "1_1") (pintype "passive"))
    )
    (net (code "42") (name "Net-(J6C-1)") (class "Default")
      (node (ref "J6") (pin "3") (pinfunction "1_3") (pintype "passive"))
      (node (ref "R23") (pin "1") (pinfunction "1_1") (pintype "passive"))
    )
    (net (code "43") (name "Net-(J6D-1)") (class "Default")
      (node (ref "J6") (pin "4") (pinfunction "1_4") (pintype "passive"))
      (node (ref "R24") (pin "1") (pinfunction "1_1") (pintype "passive"))
    )
    (net (code "44") (name "Net-(J6E-1)") (class "Default")
      (node (ref "J6") (pin "5") (pinfunction "1_5") (pintype "passive"))
      (node (ref "R25") (pin "1") (pinfunction "1_1") (pintype "passive"))
    )
    (net (code "45") (name "Net-(J7-Pad1)") (class "Default")
      (node (ref "J7") (pin "1") (pinfunction "1_1") (pintype "passive"))
      (node (ref "R26") (pin "1") (pinfunction "1_1") (pintype "passive"))
    )
    (net (code "46") (name "Net-(J7B-1)") (class "Default")
      (node (ref "J7") (pin "2") (pinfunction "1_2") (pintype "passive"))
      (node (ref "R27") (pin "1") (pinfunction "1_1") (pintype "passive"))
    )
    (net (code "47") (name "Net-(J7C-1)") (class "Default")
      (node (ref "J7") (pin "3") (pinfunction "1_3") (pintype "passive"))
      (node (ref "R28") (pin "1") (pinfunction "1_1") (pintype "passive"))
    )
    (net (code "48") (name "Net-(J7D-1)") (class "Default")
      (node (ref "J7") (pin "4") (pinfunction "1_4") (pintype "passive"))
      (node (ref "R29") (pin "1") (pinfunction "1_1") (pintype "passive"))
    )
    (net (code "49") (name "Net-(R11-S)") (class "Default")
      (node (ref "IC9") (pin "R") (pinfunction "R_R") (pintype "passive"))
      (node (ref "R11") (pin "2") (pinfunction "S_2") (pintype "passive"))
    )
    (net (code "50") (name "Net-(R32-S)") (class "Default")
      (node (ref "IC6") (pin "R") (pinfunction "R_R") (pintype "passive"))
      (node (ref "R32") (pin "2") (pinfunction "S_2") (pintype "passive"))
    )
    (net (code "51") (name "Net-(R44-S)") (class "Default")
      (node (ref "IC8") (pin "R") (pinfunction "R_R") (pintype "passive"))
      (node (ref "R44") (pin "2") (pinfunction "S_2") (pintype "passive"))
    )
    (net (code "52") (name "X_B1") (class "Default")
      (node (ref "IC2") (pin "5") (pinfunction "B1_5") (pintype "input"))
      (node (ref "R1") (pin "2") (pinfunction "2_2") (pintype "passive"))
    )
    (net (code "53") (name "X_B2") (class "Default")
      (node (ref "IC2") (pin "6") (pinfunction "B2_6") (pintype "input"))
      (node (ref "R2") (pin "2") (pinfunction "2_2") (pintype "passive"))
    )
    (net (code "54") (name "X_B3") (class "Default")
      (node (ref "IC2") (pin "7") (pinfunction "B3_7") (pintype "input"))
      (node (ref "R3") (pin "2") (pinfunction "2_2") (pintype "passive"))
    )
    (net (code "55") (name "X_B4") (class "Default")
      (node (ref "IC2") (pin "8") (pinfunction "B4_8") (pintype "input"))
      (node (ref "R4") (pin "2") (pinfunction "2_2") (pintype "passive"))
    )
    (net (code "56") (name "X_B5") (class "Default")
      (node (ref "IC2") (pin "9") (pinfunction "B5_9") (pintype "input"))
      (node (ref "R5") (pin "2") (pinfunction "2_2") (pintype "passive"))
    )
    (net (code "57") (name "X_B6") (class "Default")
      (node (ref "IC2") (pin "10") (pinfunction "B6_10") (pintype "input"))
      (node (ref "R6") (pin "2") (pinfunction "2_2") (pintype "passive"))
    )
    (net (code "58") (name "X_B7") (class "Default")
      (node (ref "IC2") (pin "11") (pinfunction "B7_11") (pintype "input"))
      (node (ref "R7") (pin "2") (pinfunction "2_2") (pintype "passive"))
    )
    (net (code "59") (name "X_B8") (class "Default")
      (node (ref "IC2") (pin "12") (pinfunction "B8_12") (pintype "input"))
      (node (ref "R8") (pin "2") (pinfunction "2_2") (pintype "passive"))
    )
    (net (code "60") (name "X_DAC_OUT") (class "Default")
      (node (ref "C13") (pin "2") (pinfunction "2_2") (pintype "passive"))
      (node (ref "IC2") (pin "4") (pinfunction "IOUT_4") (pintype "output"))
    )
    (net (code "61") (name "X_VREF") (class "Default")
      (node (ref "C4") (pin "+") (pinfunction "+_+") (pintype "passive"))
      (node (ref "IC9") (pin "C") (pinfunction "C_C") (pintype "passive"))
      (node (ref "R10") (pin "2") (pinfunction "2_2") (pintype "passive"))
      (node (ref "R11") (pin "1") (pinfunction "E_1") (pintype "passive"))
      (node (ref "R12") (pin "1") (pinfunction "1_1") (pintype "passive"))
    )
    (net (code "62") (name "Y_B1") (class "Default")
      (node (ref "IC5") (pin "5") (pinfunction "B1_5") (pintype "input"))
      (node (ref "R22") (pin "2") (pinfunction "2_2") (pintype "passive"))
    )
    (net (code "63") (name "Y_B2") (class "Default")
      (node (ref "IC5") (pin "6") (pinfunction "B2_6") (pintype "input"))
      (node (ref "R23") (pin "2") (pinfunction "2_2") (pintype "passive"))
    )
    (net (code "64") (name "Y_B3") (class "Default")
      (node (ref "IC5") (pin "7") (pinfunction "B3_7") (pintype "input"))
      (node (ref "R24") (pin "2") (pinfunction "2_2") (pintype "passive"))
    )
    (net (code "65") (name "Y_B4") (class "Default")
      (node (ref "IC5") (pin "8") (pinfunction "B4_8") (pintype "input"))
      (node (ref "R25") (pin "2") (pinfunction "2_2") (pintype "passive"))
    )
    (net (code "66") (name "Y_B5") (class "Default")
      (node (ref "IC5") (pin "9") (pinfunction "B5_9") (pintype "input"))
      (node (ref "R26") (pin "2") (pinfunction "2_2") (pintype "passive"))
    )
    (net (code "67") (name "Y_B6") (class "Default")
      (node (ref "IC5") (pin "10") (pinfunction "B6_10") (pintype "input"))
      (node (ref "R27") (pin "2") (pinfunction "2_2") (pintype "passive"))
    )
    (net (code "68") (name "Y_B7") (class "Default")
      (node (ref "IC5") (pin "11") (pinfunction "B7_11") (pintype "input"))
      (node (ref "R28") (pin "2") (pinfunction "2_2") (pintype "passive"))
    )
    (net (code "69") (name "Y_B8") (class "Default")
      (node (ref "IC5") (pin "12") (pinfunction "B8_12") (pintype "input"))
      (node (ref "R29") (pin "2") (pinfunction "2_2") (pintype "passive"))
    )
    (net (code "70") (name "Y_DAC_OUT") (class "Default")
      (node (ref "C16") (pin "2") (pinfunction "2_2") (pintype "passive"))
      (node (ref "IC5") (pin "4") (pinfunction "IOUT_4") (pintype "output"))
    )
    (net (code "71") (name "Y_VREF") (class "Default")
      (node (ref "C29") (pin "+") (pinfunction "+_+") (pintype "passive"))
      (node (ref "IC6") (pin "C") (pinfunction "C_C") (pintype "passive"))
      (node (ref "R31") (pin "2") (pinfunction "2_2") (pintype "passive"))
      (node (ref "R32") (pin "1") (pinfunction "E_1") (pintype "passive"))
      (node (ref "R33") (pin "1") (pinfunction "1_1") (pintype "passive"))
    )
    (net (code "72") (name "Z_B1") (class "Default")
      (node (ref "IC7") (pin "5") (pinfunction "B1_5") (pintype "input"))
      (node (ref "R34") (pin "2") (pinfunction "2_2") (pintype "passive"))
    )
    (net (code "73") (name "Z_B2") (class "Default")
      (node (ref "IC7") (pin "6") (pinfunction "B2_6") (pintype "input"))
      (node (ref "R35") (pin "2") (pinfunction "2_2") (pintype "passive"))
    )
    (net (code "74") (name "Z_B3") (class "Default")
      (node (ref "IC7") (pin "7") (pinfunction "B3_7") (pintype "input"))
      (node (ref "R36") (pin "2") (pinfunction "2_2") (pintype "passive"))
    )
    (net (code "75") (name "Z_B4") (class "Default")
      (node (ref "IC7") (pin "8") (pinfunction "B4_8") (pintype "input"))
      (node (ref "R37") (pin "2") (pinfunction "2_2") (pintype "passive"))
    )
    (net (code "76") (name "Z_B5") (class "Default")
      (node (ref "IC7") (pin "9") (pinfunction "B5_9") (pintype "input"))
      (node (ref "R38") (pin "2") (pinfunction "2_2") (pintype "passive"))
    )
    (net (code "77") (name "Z_B6") (class "Default")
      (node (ref "IC7") (pin "10") (pinfunction "B6_10") (pintype "input"))
      (node (ref "R39") (pin "2") (pinfunction "2_2") (pintype "passive"))
    )
    (net (code "78") (name "Z_B7") (class "Default")
      (node (ref "IC7") (pin "11") (pinfunction "B7_11") (pintype "input"))
      (node (ref "R40") (pin "2") (pinfunction "2_2") (pintype "passive"))
    )
    (net (code "79") (name "Z_B8") (class "Default")
      (node (ref "IC7") (pin "12") (pinfunction "B8_12") (pintype "input"))
      (node (ref "R41") (pin "2") (pinfunction "2_2") (pintype "passive"))
    )
    (net (code "80") (name "Z_DAC_OUT") (class "Default")
      (node (ref "C25") (pin "2") (pinfunction "2_2") (pintype "passive"))
      (node (ref "IC7") (pin "4") (pinfunction "IOUT_4") (pintype "output"))
    )
    (net (code "81") (name "Z_VREF") (class "Default")
      (node (ref "C33") (pin "+") (pinfunction "+_+") (pintype "passive"))
      (node (ref "IC8") (pin "C") (pinfunction "C_C") (pintype "passive"))
      (node (ref "R43") (pin "2") (pinfunction "2_2") (pintype "passive"))
      (node (ref "R44") (pin "1") (pinfunction "E_1") (pintype "passive"))
      (node (ref "R45") (pin "1") (pinfunction "1_1") (pintype "passive"))
    )
  )
)
